# I-O_Connectors.net
KiCad netlist of a schematic drawn in Altium Designer
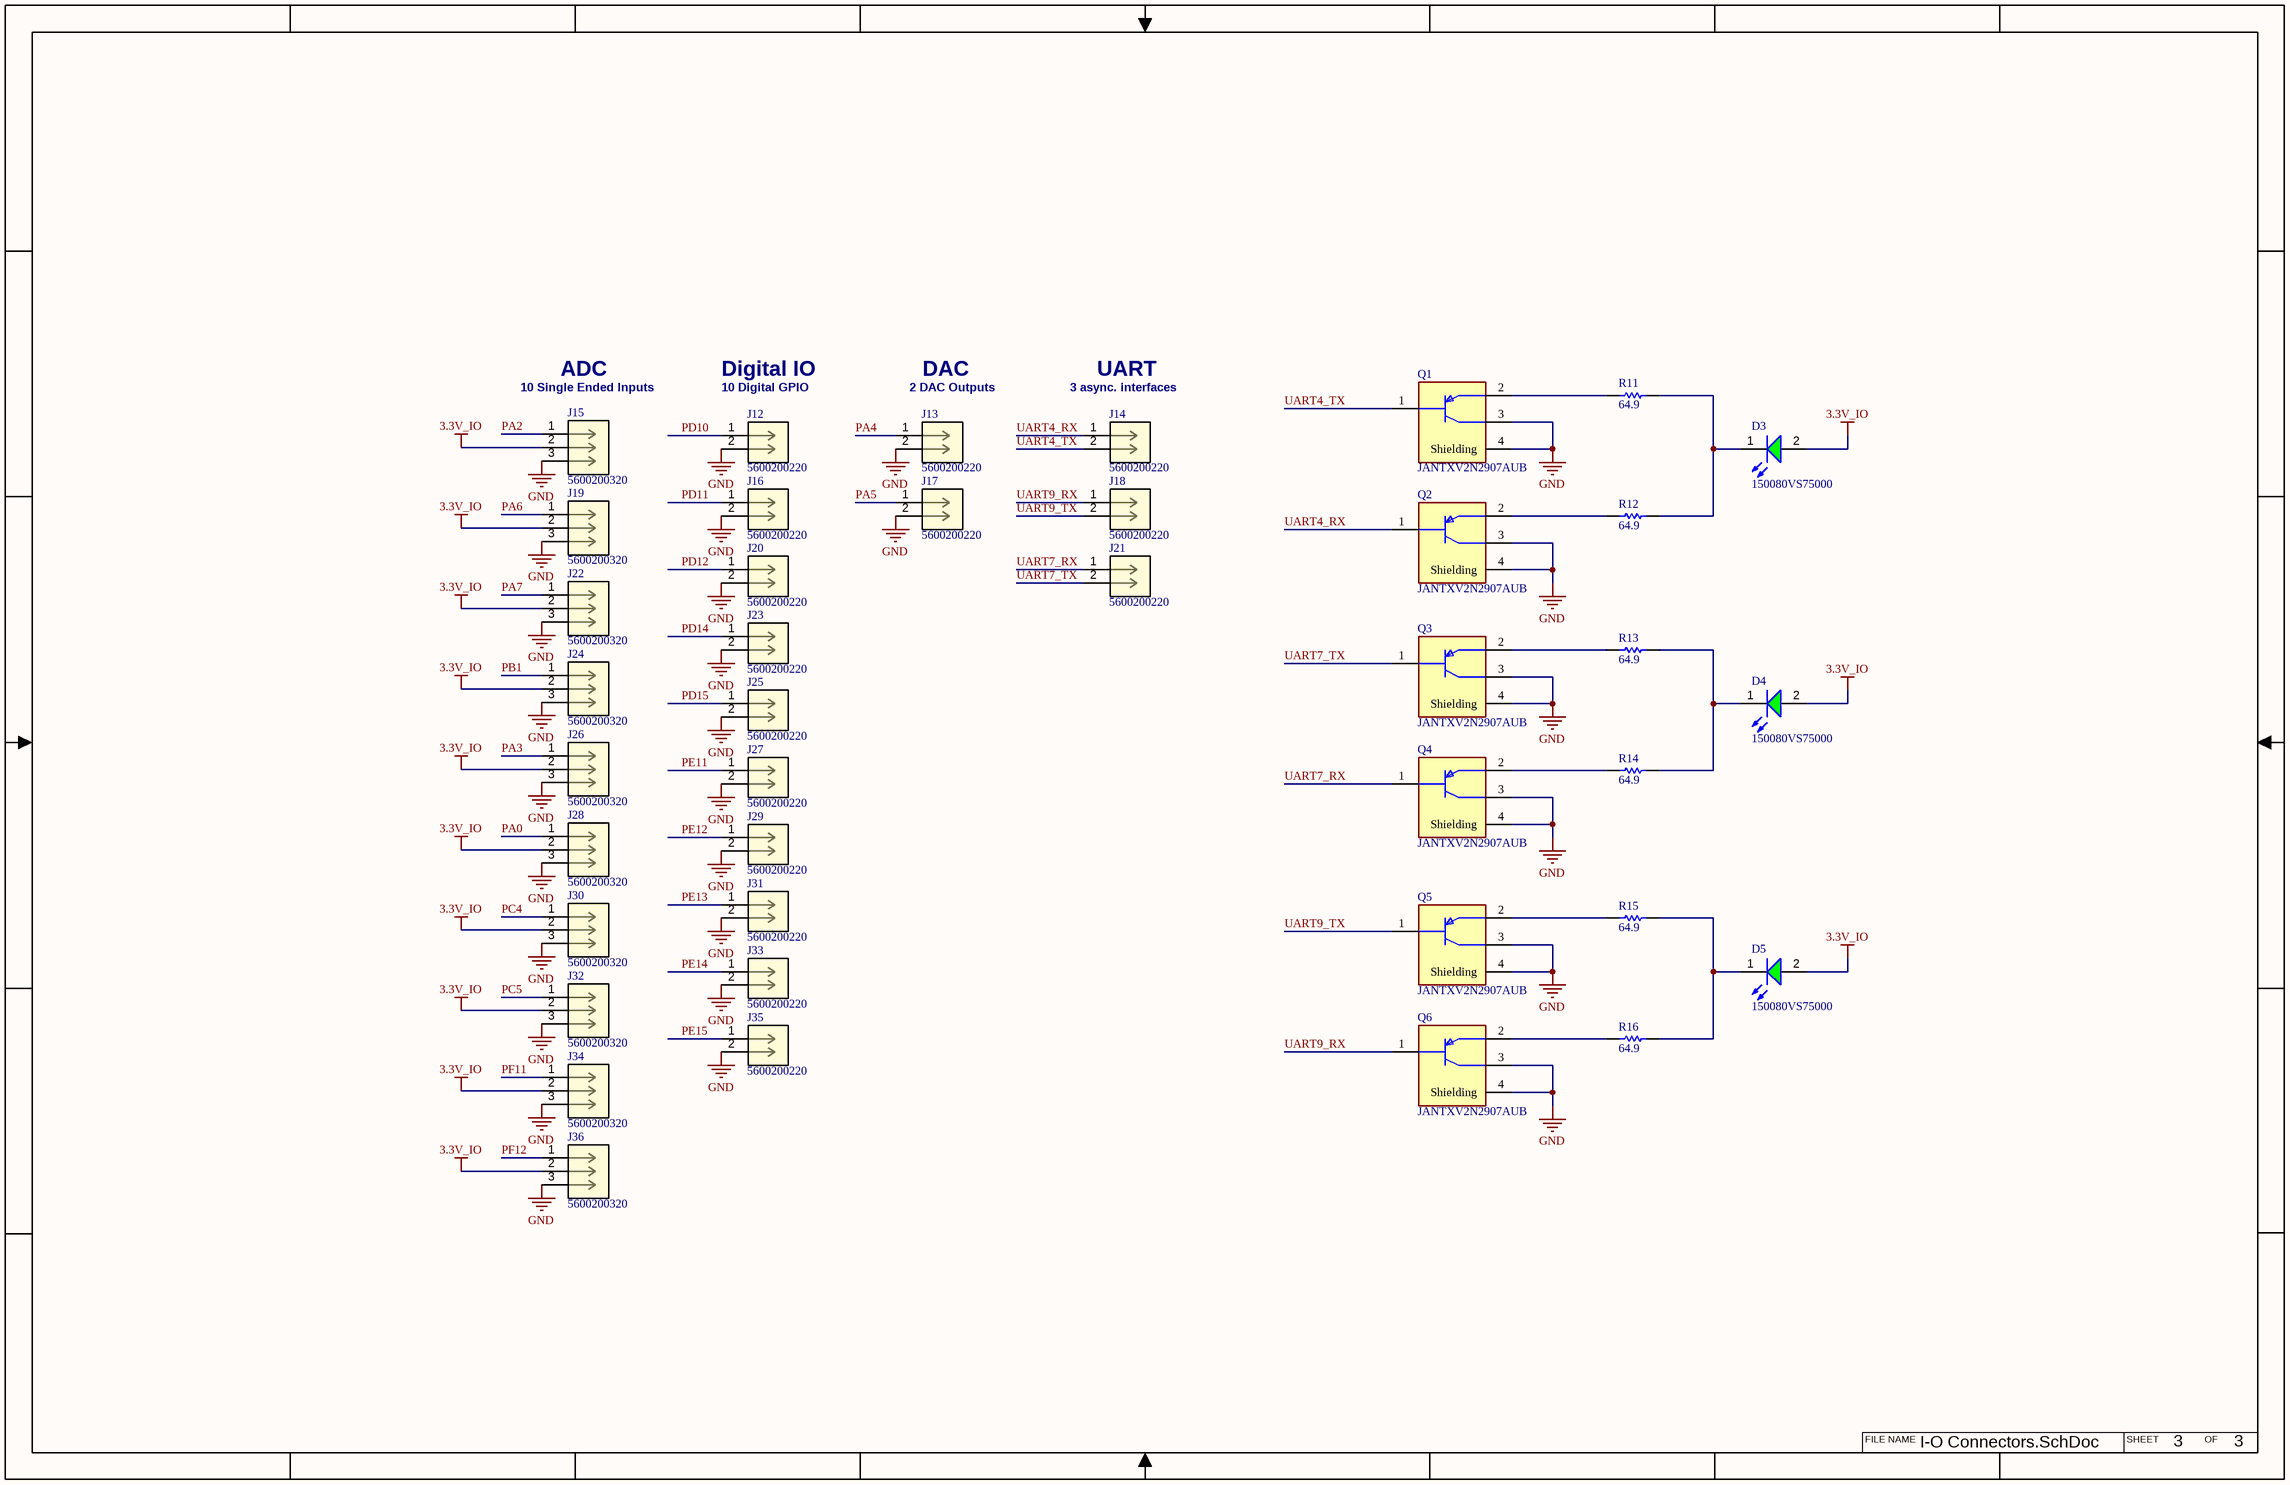
[diagram p0: I-O Connectors.SchDoc]

(export (version "E")
  (design (tool "Eeschema 10.0.6"))
  (components
    (comp (ref "D3")
      (value "150080VS75000")
      (footprint "WL-SMCW_0805_150080xx75000")
      (description "WL-SMCW SMT Mono-Color Chip LED Waterclear")
      (libsource (lib "Altium Content Vault") (part "LED_Green_2A-1K"))
    )
    (comp (ref "D4")
      (value "150080VS75000")
      (footprint "WL-SMCW_0805_150080xx75000")
      (description "WL-SMCW SMT Mono-Color Chip LED Waterclear")
      (libsource (lib "Altium Content Vault") (part "LED_Green_2A-1K"))
    )
    (comp (ref "D5")
      (value "150080VS75000")
      (footprint "WL-SMCW_0805_150080xx75000")
      (description "WL-SMCW SMT Mono-Color Chip LED Waterclear")
      (libsource (lib "Altium Content Vault") (part "LED_Green_2A-1K"))
    )
    (comp (ref "J12")
      (value "5600200220")
      (footprint "CONN_5600200220_MOL")
      (description "No Description Available")
      (libsource (lib "5600200220") (part "5600200220"))
    )
    (comp (ref "J13")
      (value "5600200220")
      (footprint "CONN_5600200220_MOL")
      (description "No Description Available")
      (libsource (lib "5600200220") (part "5600200220"))
    )
    (comp (ref "J14")
      (value "5600200220")
      (footprint "CONN_5600200220_MOL")
      (description "No Description Available")
      (libsource (lib "5600200220") (part "5600200220"))
    )
    (comp (ref "J15")
      (value "5600200320")
      (footprint "CONN03_560020_MOL")
      (description "No Description Available")
      (libsource (lib "5600200320") (part "5600200320"))
    )
    (comp (ref "J16")
      (value "5600200220")
      (footprint "CONN_5600200220_MOL")
      (description "No Description Available")
      (libsource (lib "5600200220") (part "5600200220"))
    )
    (comp (ref "J17")
      (value "5600200220")
      (footprint "CONN_5600200220_MOL")
      (description "No Description Available")
      (libsource (lib "5600200220") (part "5600200220"))
    )
    (comp (ref "J18")
      (value "5600200220")
      (footprint "CONN_5600200220_MOL")
      (description "No Description Available")
      (libsource (lib "5600200220") (part "5600200220"))
    )
    (comp (ref "J19")
      (value "5600200320")
      (footprint "CONN03_560020_MOL")
      (description "No Description Available")
      (libsource (lib "5600200320") (part "5600200320"))
    )
    (comp (ref "J20")
      (value "5600200220")
      (footprint "CONN_5600200220_MOL")
      (description "No Description Available")
      (libsource (lib "5600200220") (part "5600200220"))
    )
    (comp (ref "J21")
      (value "5600200220")
      (footprint "CONN_5600200220_MOL")
      (description "No Description Available")
      (libsource (lib "5600200220") (part "5600200220"))
    )
    (comp (ref "J22")
      (value "5600200320")
      (footprint "CONN03_560020_MOL")
      (description "No Description Available")
      (libsource (lib "5600200320") (part "5600200320"))
    )
    (comp (ref "J23")
      (value "5600200220")
      (footprint "CONN_5600200220_MOL")
      (description "No Description Available")
      (libsource (lib "5600200220") (part "5600200220"))
    )
    (comp (ref "J24")
      (value "5600200320")
      (footprint "CONN03_560020_MOL")
      (description "No Description Available")
      (libsource (lib "5600200320") (part "5600200320"))
    )
    (comp (ref "J25")
      (value "5600200220")
      (footprint "CONN_5600200220_MOL")
      (description "No Description Available")
      (libsource (lib "5600200220") (part "5600200220"))
    )
    (comp (ref "J26")
      (value "5600200320")
      (footprint "CONN03_560020_MOL")
      (description "No Description Available")
      (libsource (lib "5600200320") (part "5600200320"))
    )
    (comp (ref "J27")
      (value "5600200220")
      (footprint "CONN_5600200220_MOL")
      (description "No Description Available")
      (libsource (lib "5600200220") (part "5600200220"))
    )
    (comp (ref "J28")
      (value "5600200320")
      (footprint "CONN03_560020_MOL")
      (description "No Description Available")
      (libsource (lib "5600200320") (part "5600200320"))
    )
    (comp (ref "J29")
      (value "5600200220")
      (footprint "CONN_5600200220_MOL")
      (description "No Description Available")
      (libsource (lib "5600200220") (part "5600200220"))
    )
    (comp (ref "J30")
      (value "5600200320")
      (footprint "CONN03_560020_MOL")
      (description "No Description Available")
      (libsource (lib "5600200320") (part "5600200320"))
    )
    (comp (ref "J31")
      (value "5600200220")
      (footprint "CONN_5600200220_MOL")
      (description "No Description Available")
      (libsource (lib "5600200220") (part "5600200220"))
    )
    (comp (ref "J32")
      (value "5600200320")
      (footprint "CONN03_560020_MOL")
      (description "No Description Available")
      (libsource (lib "5600200320") (part "5600200320"))
    )
    (comp (ref "J33")
      (value "5600200220")
      (footprint "CONN_5600200220_MOL")
      (description "No Description Available")
      (libsource (lib "5600200220") (part "5600200220"))
    )
    (comp (ref "J34")
      (value "5600200320")
      (footprint "CONN03_560020_MOL")
      (description "No Description Available")
      (libsource (lib "5600200320") (part "5600200320"))
    )
    (comp (ref "J35")
      (value "5600200220")
      (footprint "CONN_5600200220_MOL")
      (description "No Description Available")
      (libsource (lib "5600200220") (part "5600200220"))
    )
    (comp (ref "J36")
      (value "5600200320")
      (footprint "CONN03_560020_MOL")
      (description "No Description Available")
      (libsource (lib "5600200320") (part "5600200320"))
    )
    (comp (ref "Q1")
      (value "JANTXV2N2907AUB")
      (footprint "FP-UB-IPC_C")
      (description "TRANS PNP 60V 0.6A 4UB")
      (libsource (lib "Altium Content Vault") (part "0d70041905f6d5555c09c601eb40e03"))
    )
    (comp (ref "Q2")
      (value "JANTXV2N2907AUB")
      (footprint "FP-UB-IPC_C")
      (description "TRANS PNP 60V 0.6A 4UB")
      (libsource (lib "Altium Content Vault") (part "0d70041905f6d5555c09c601eb40e03"))
    )
    (comp (ref "Q3")
      (value "JANTXV2N2907AUB")
      (footprint "FP-UB-IPC_C")
      (description "TRANS PNP 60V 0.6A 4UB")
      (libsource (lib "Altium Content Vault") (part "0d70041905f6d5555c09c601eb40e03"))
    )
    (comp (ref "Q4")
      (value "JANTXV2N2907AUB")
      (footprint "FP-UB-IPC_C")
      (description "TRANS PNP 60V 0.6A 4UB")
      (libsource (lib "Altium Content Vault") (part "0d70041905f6d5555c09c601eb40e03"))
    )
    (comp (ref "Q5")
      (value "JANTXV2N2907AUB")
      (footprint "FP-UB-IPC_C")
      (description "TRANS PNP 60V 0.6A 4UB")
      (libsource (lib "Altium Content Vault") (part "0d70041905f6d5555c09c601eb40e03"))
    )
    (comp (ref "Q6")
      (value "JANTXV2N2907AUB")
      (footprint "FP-UB-IPC_C")
      (description "TRANS PNP 60V 0.6A 4UB")
      (libsource (lib "Altium Content Vault") (part "0d70041905f6d5555c09c601eb40e03"))
    )
    (comp (ref "R11")
      (value "64.9")
      (footprint "RESC2013X60X35LL10T20")
      (fields (field (name "PART NUMBER") "RC0805FR-0764R9L") (field (name "MANUFACTURER") "Yageo"))
      (libsource (lib "Altium Content Vault") (part "RES"))
    )
    (comp (ref "R12")
      (value "64.9")
      (footprint "RESC2013X60X35LL10T20")
      (fields (field (name "PART NUMBER") "RC0805FR-0764R9L") (field (name "MANUFACTURER") "Yageo"))
      (libsource (lib "Altium Content Vault") (part "RES"))
    )
    (comp (ref "R13")
      (value "64.9")
      (footprint "RESC2013X60X35LL10T20")
      (fields (field (name "PART NUMBER") "RC0805FR-0764R9L") (field (name "MANUFACTURER") "Yageo"))
      (libsource (lib "Altium Content Vault") (part "RES"))
    )
    (comp (ref "R14")
      (value "64.9")
      (footprint "RESC2013X60X35LL10T20")
      (fields (field (name "PART NUMBER") "RC0805FR-0764R9L") (field (name "MANUFACTURER") "Yageo"))
      (libsource (lib "Altium Content Vault") (part "RES"))
    )
    (comp (ref "R15")
      (value "64.9")
      (footprint "RESC2013X60X35LL10T20")
      (fields (field (name "PART NUMBER") "RC0805FR-0764R9L") (field (name "MANUFACTURER") "Yageo"))
      (libsource (lib "Altium Content Vault") (part "RES"))
    )
    (comp (ref "R16")
      (value "64.9")
      (footprint "RESC2013X60X35LL10T20")
      (fields (field (name "PART NUMBER") "RC0805FR-0764R9L") (field (name "MANUFACTURER") "Yageo"))
      (libsource (lib "Altium Content Vault") (part "RES"))
    )
  )
  (nets
    (net (code "1") (name "/PA0") (class "Default")
      (node (ref "J28") (pin "1") (pinfunction "1_1") (pintype "passive"))
    )
    (net (code "2") (name "/PA2") (class "Default")
      (node (ref "J15") (pin "1") (pinfunction "1_1") (pintype "passive"))
    )
    (net (code "3") (name "/PA3") (class "Default")
      (node (ref "J26") (pin "1") (pinfunction "1_1") (pintype "passive"))
    )
    (net (code "4") (name "/PA4") (class "Default")
      (node (ref "J13") (pin "1") (pinfunction "1_1") (pintype "passive"))
    )
    (net (code "5") (name "/PA5") (class "Default")
      (node (ref "J17") (pin "1") (pinfunction "1_1") (pintype "passive"))
    )
    (net (code "6") (name "/PA6") (class "Default")
      (node (ref "J19") (pin "1") (pinfunction "1_1") (pintype "passive"))
    )
    (net (code "7") (name "/PA7") (class "Default")
      (node (ref "J22") (pin "1") (pinfunction "1_1") (pintype "passive"))
    )
    (net (code "8") (name "/PB1") (class "Default")
      (node (ref "J24") (pin "1") (pinfunction "1_1") (pintype "passive"))
    )
    (net (code "9") (name "/PC4") (class "Default")
      (node (ref "J30") (pin "1") (pinfunction "1_1") (pintype "passive"))
    )
    (net (code "10") (name "/PC5") (class "Default")
      (node (ref "J32") (pin "1") (pinfunction "1_1") (pintype "passive"))
    )
    (net (code "11") (name "/PD10") (class "Default")
      (node (ref "J12") (pin "1") (pinfunction "1_1") (pintype "passive"))
    )
    (net (code "12") (name "/PD11") (class "Default")
      (node (ref "J16") (pin "1") (pinfunction "1_1") (pintype "passive"))
    )
    (net (code "13") (name "/PD12") (class "Default")
      (node (ref "J20") (pin "1") (pinfunction "1_1") (pintype "passive"))
    )
    (net (code "14") (name "/PD14") (class "Default")
      (node (ref "J23") (pin "1") (pinfunction "1_1") (pintype "passive"))
    )
    (net (code "15") (name "/PD15") (class "Default")
      (node (ref "J25") (pin "1") (pinfunction "1_1") (pintype "passive"))
    )
    (net (code "16") (name "/PE11") (class "Default")
      (node (ref "J27") (pin "1") (pinfunction "1_1") (pintype "passive"))
    )
    (net (code "17") (name "/PE12") (class "Default")
      (node (ref "J29") (pin "1") (pinfunction "1_1") (pintype "passive"))
    )
    (net (code "18") (name "/PE13") (class "Default")
      (node (ref "J31") (pin "1") (pinfunction "1_1") (pintype "passive"))
    )
    (net (code "19") (name "/PE14") (class "Default")
      (node (ref "J33") (pin "1") (pinfunction "1_1") (pintype "passive"))
    )
    (net (code "20") (name "/PE15") (class "Default")
      (node (ref "J35") (pin "1") (pinfunction "1_1") (pintype "passive"))
    )
    (net (code "21") (name "/PF11") (class "Default")
      (node (ref "J34") (pin "1") (pinfunction "1_1") (pintype "passive"))
    )
    (net (code "22") (name "/PF12") (class "Default")
      (node (ref "J36") (pin "1") (pinfunction "1_1") (pintype "passive"))
    )
    (net (code "23") (name "/UART4_RX") (class "Default")
      (node (ref "J14") (pin "1") (pinfunction "1_1") (pintype "passive"))
      (node (ref "Q2") (pin "1") (pinfunction "B_1") (pintype "passive"))
    )
    (net (code "24") (name "/UART4_TX") (class "Default")
      (node (ref "J14") (pin "2") (pinfunction "2_2") (pintype "passive"))
      (node (ref "Q1") (pin "1") (pinfunction "B_1") (pintype "passive"))
    )
    (net (code "25") (name "/UART7_RX") (class "Default")
      (node (ref "J21") (pin "1") (pinfunction "1_1") (pintype "passive"))
      (node (ref "Q4") (pin "1") (pinfunction "B_1") (pintype "passive"))
    )
    (net (code "26") (name "/UART7_TX") (class "Default")
      (node (ref "J21") (pin "2") (pinfunction "2_2") (pintype "passive"))
      (node (ref "Q3") (pin "1") (pinfunction "B_1") (pintype "passive"))
    )
    (net (code "27") (name "/UART9_RX") (class "Default")
      (node (ref "J18") (pin "1") (pinfunction "1_1") (pintype "passive"))
      (node (ref "Q6") (pin "1") (pinfunction "B_1") (pintype "passive"))
    )
    (net (code "28") (name "/UART9_TX") (class "Default")
      (node (ref "J18") (pin "2") (pinfunction "2_2") (pintype "passive"))
      (node (ref "Q5") (pin "1") (pinfunction "B_1") (pintype "passive"))
    )
    (net (code "29") (name "3.3V_IO") (class "Default")
      (node (ref "D3") (pin "2") (pinfunction "A_2") (pintype "passive"))
      (node (ref "D4") (pin "2") (pinfunction "A_2") (pintype "passive"))
      (node (ref "D5") (pin "2") (pinfunction "A_2") (pintype "passive"))
      (node (ref "J15") (pin "2") (pinfunction "2_2") (pintype "passive"))
      (node (ref "J19") (pin "2") (pinfunction "2_2") (pintype "passive"))
      (node (ref "J22") (pin "2") (pinfunction "2_2") (pintype "passive"))
      (node (ref "J24") (pin "2") (pinfunction "2_2") (pintype "passive"))
      (node (ref "J26") (pin "2") (pinfunction "2_2") (pintype "passive"))
      (node (ref "J28") (pin "2") (pinfunction "2_2") (pintype "passive"))
      (node (ref "J30") (pin "2") (pinfunction "2_2") (pintype "passive"))
      (node (ref "J32") (pin "2") (pinfunction "2_2") (pintype "passive"))
      (node (ref "J34") (pin "2") (pinfunction "2_2") (pintype "passive"))
      (node (ref "J36") (pin "2") (pinfunction "2_2") (pintype "passive"))
    )
    (net (code "30") (name "GND") (class "Default")
      (node (ref "J12") (pin "2") (pinfunction "2_2") (pintype "passive"))
      (node (ref "J13") (pin "2") (pinfunction "2_2") (pintype "passive"))
      (node (ref "J15") (pin "3") (pinfunction "3_3") (pintype "passive"))
      (node (ref "J16") (pin "2") (pinfunction "2_2") (pintype "passive"))
      (node (ref "J17") (pin "2") (pinfunction "2_2") (pintype "passive"))
      (node (ref "J19") (pin "3") (pinfunction "3_3") (pintype "passive"))
      (node (ref "J20") (pin "2") (pinfunction "2_2") (pintype "passive"))
      (node (ref "J22") (pin "3") (pinfunction "3_3") (pintype "passive"))
      (node (ref "J23") (pin "2") (pinfunction "2_2") (pintype "passive"))
      (node (ref "J24") (pin "3") (pinfunction "3_3") (pintype "passive"))
      (node (ref "J25") (pin "2") (pinfunction "2_2") (pintype "passive"))
      (node (ref "J26") (pin "3") (pinfunction "3_3") (pintype "passive"))
      (node (ref "J27") (pin "2") (pinfunction "2_2") (pintype "passive"))
      (node (ref "J28") (pin "3") (pinfunction "3_3") (pintype "passive"))
      (node (ref "J29") (pin "2") (pinfunction "2_2") (pintype "passive"))
      (node (ref "J30") (pin "3") (pinfunction "3_3") (pintype "passive"))
      (node (ref "J31") (pin "2") (pinfunction "2_2") (pintype "passive"))
      (node (ref "J32") (pin "3") (pinfunction "3_3") (pintype "passive"))
      (node (ref "J33") (pin "2") (pinfunction "2_2") (pintype "passive"))
      (node (ref "J34") (pin "3") (pinfunction "3_3") (pintype "passive"))
      (node (ref "J35") (pin "2") (pinfunction "2_2") (pintype "passive"))
      (node (ref "J36") (pin "3") (pinfunction "3_3") (pintype "passive"))
      (node (ref "Q1") (pin "3") (pinfunction "C_3") (pintype "passive"))
      (node (ref "Q1") (pin "4") (pinfunction "Shielding_4") (pintype "passive"))
      (node (ref "Q2") (pin "3") (pinfunction "C_3") (pintype "passive"))
      (node (ref "Q2") (pin "4") (pinfunction "Shielding_4") (pintype "passive"))
      (node (ref "Q3") (pin "3") (pinfunction "C_3") (pintype "passive"))
      (node (ref "Q3") (pin "4") (pinfunction "Shielding_4") (pintype "passive"))
      (node (ref "Q4") (pin "3") (pinfunction "C_3") (pintype "passive"))
      (node (ref "Q4") (pin "4") (pinfunction "Shielding_4") (pintype "passive"))
      (node (ref "Q5") (pin "3") (pinfunction "C_3") (pintype "passive"))
      (node (ref "Q5") (pin "4") (pinfunction "Shielding_4") (pintype "passive"))
      (node (ref "Q6") (pin "3") (pinfunction "C_3") (pintype "passive"))
      (node (ref "Q6") (pin "4") (pinfunction "Shielding_4") (pintype "passive"))
    )
    (net (code "31") (name "Net-(D3-K)") (class "Default")
      (node (ref "D3") (pin "1") (pinfunction "K_1") (pintype "passive"))
      (node (ref "R11") (pin "1") (pinfunction "1_1") (pintype "passive"))
      (node (ref "R12") (pin "1") (pinfunction "1_1") (pintype "passive"))
    )
    (net (code "32") (name "Net-(D4-K)") (class "Default")
      (node (ref "D4") (pin "1") (pinfunction "K_1") (pintype "passive"))
      (node (ref "R13") (pin "1") (pinfunction "1_1") (pintype "passive"))
      (node (ref "R14") (pin "1") (pinfunction "1_1") (pintype "passive"))
    )
    (net (code "33") (name "Net-(D5-K)") (class "Default")
      (node (ref "D5") (pin "1") (pinfunction "K_1") (pintype "passive"))
      (node (ref "R15") (pin "1") (pinfunction "1_1") (pintype "passive"))
      (node (ref "R16") (pin "1") (pinfunction "1_1") (pintype "passive"))
    )
    (net (code "34") (name "Net-(Q1-E)") (class "Default")
      (node (ref "Q1") (pin "2") (pinfunction "E_2") (pintype "passive"))
      (node (ref "R11") (pin "2") (pinfunction "2_2") (pintype "passive"))
    )
    (net (code "35") (name "Net-(Q2-E)") (class "Default")
      (node (ref "Q2") (pin "2") (pinfunction "E_2") (pintype "passive"))
      (node (ref "R12") (pin "2") (pinfunction "2_2") (pintype "passive"))
    )
    (net (code "36") (name "Net-(Q3-E)") (class "Default")
      (node (ref "Q3") (pin "2") (pinfunction "E_2") (pintype "passive"))
      (node (ref "R13") (pin "2") (pinfunction "2_2") (pintype "passive"))
    )
    (net (code "37") (name "Net-(Q4-E)") (class "Default")
      (node (ref "Q4") (pin "2") (pinfunction "E_2") (pintype "passive"))
      (node (ref "R14") (pin "2") (pinfunction "2_2") (pintype "passive"))
    )
    (net (code "38") (name "Net-(Q5-E)") (class "Default")
      (node (ref "Q5") (pin "2") (pinfunction "E_2") (pintype "passive"))
      (node (ref "R15") (pin "2") (pinfunction "2_2") (pintype "passive"))
    )
    (net (code "39") (name "Net-(Q6-E)") (class "Default")
      (node (ref "Q6") (pin "2") (pinfunction "E_2") (pintype "passive"))
      (node (ref "R16") (pin "2") (pinfunction "2_2") (pintype "passive"))
    )
  )
)
